# Indictor.net
KiCad netlist of a schematic drawn in Altium Designer
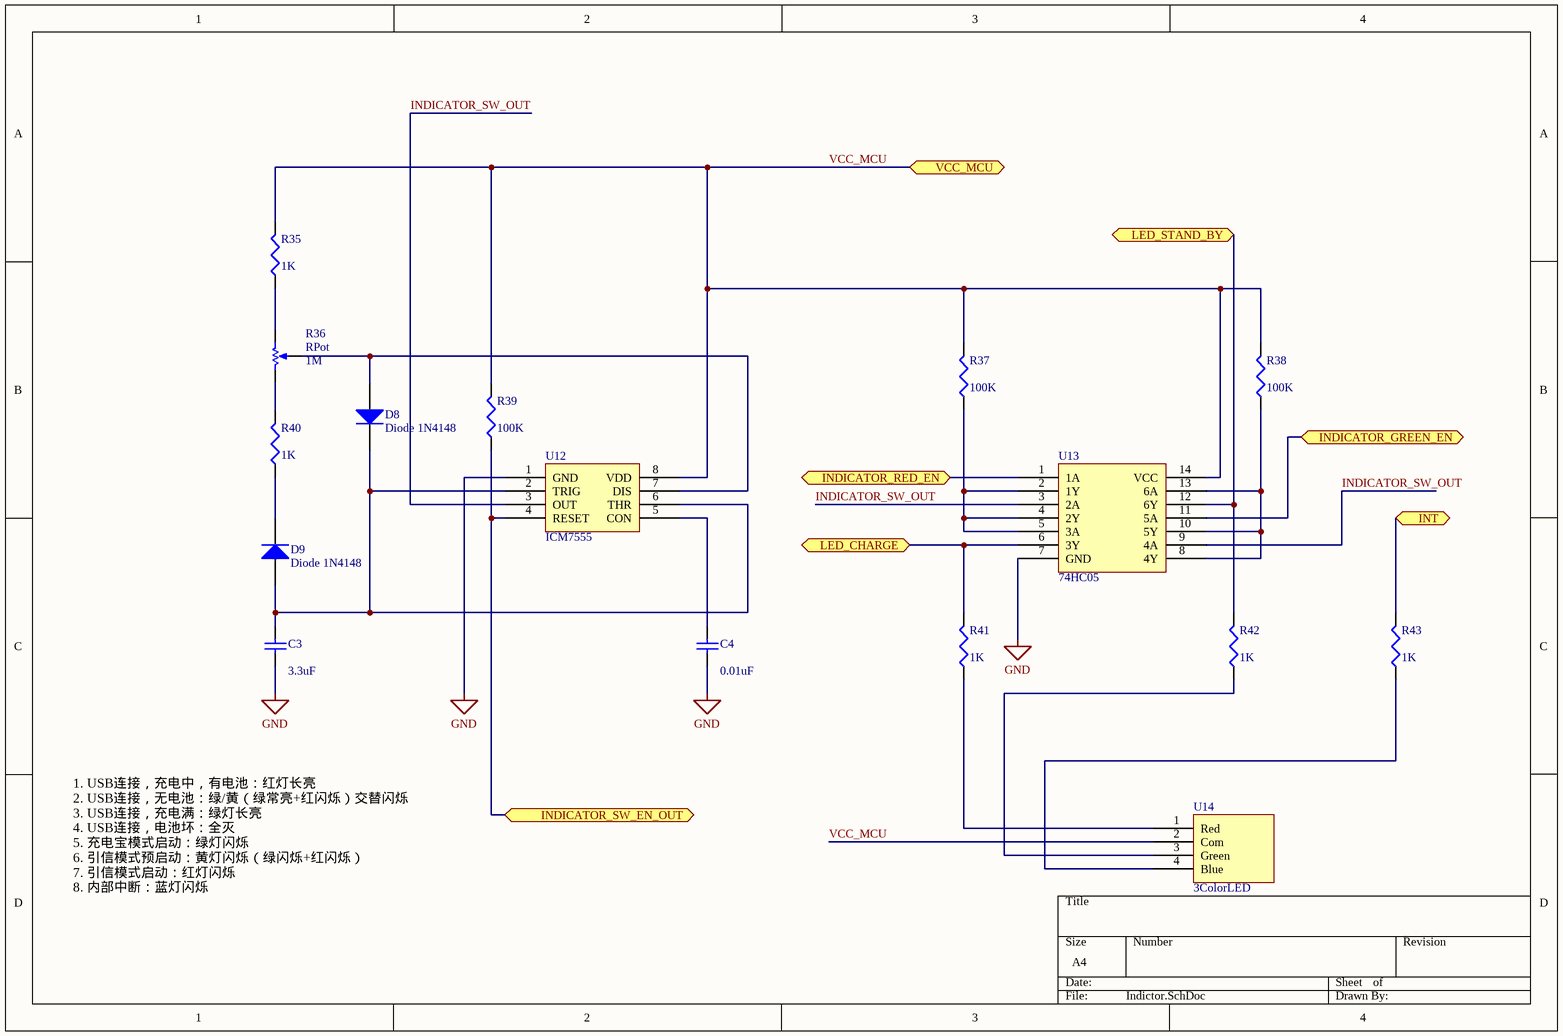
[diagram p0: Indictor.SchDoc]

(export (version "E")
  (design (tool "Eeschema 10.0.6"))
  (components
    (comp (ref "C3")
      (value "3.3uF")
      (footprint "clock:0603")
      (description "Capacitor (Semiconductor SIM Model)")
      (fields (field (name "Comment") "Cap Semi") (field (name "PUBLISHER") "Altium Limited"))
      (libsource (lib "Miscellaneous Devices") (part "Cap Semi"))
    )
    (comp (ref "C4")
      (value "0.01uF")
      (footprint "clock:0603")
      (description "Capacitor (Semiconductor SIM Model)")
      (fields (field (name "Comment") "Cap Semi") (field (name "PUBLISHER") "Altium Limited"))
      (libsource (lib "Miscellaneous Devices") (part "Cap Semi"))
    )
    (comp (ref "D8")
      (value "Diode 1N4148")
      (footprint "clock:1206D")
      (description "1 Amp General Purpose Rectifier")
      (fields (field (name "PUBLISHER") "Altium Limited"))
      (libsource (lib "Miscellaneous Devices") (part "Diode 1N4005"))
    )
    (comp (ref "D9")
      (value "Diode 1N4148")
      (footprint "clock:1206D")
      (description "1 Amp General Purpose Rectifier")
      (fields (field (name "PUBLISHER") "Altium Limited"))
      (libsource (lib "Miscellaneous Devices") (part "Diode 1N4005"))
    )
    (comp (ref "R35")
      (value "1K")
      (footprint "clock:0603")
      (description "Resistor")
      (fields (field (name "Comment") "Res3") (field (name "PUBLISHER") "Altium Limited"))
      (libsource (lib "Miscellaneous Devices") (part "Res3"))
    )
    (comp (ref "R36")
      (value "RPot")
      (footprint "clock:VR5")
      (description "Potentiometer")
      (fields (field (name "ALTIUM_VALUE") "1M") (field (name "PUBLISHER") "Altium Limited"))
      (libsource (lib "Miscellaneous Devices") (part "RPot"))
    )
    (comp (ref "R37")
      (value "100K")
      (footprint "clock:0603")
      (description "Resistor")
      (fields (field (name "Comment") "Res3") (field (name "PUBLISHER") "Altium Limited"))
      (libsource (lib "Miscellaneous Devices") (part "Res3"))
    )
    (comp (ref "R38")
      (value "100K")
      (footprint "clock:0603")
      (description "Resistor")
      (fields (field (name "Comment") "Res3") (field (name "PUBLISHER") "Altium Limited"))
      (libsource (lib "Miscellaneous Devices") (part "Res3"))
    )
    (comp (ref "R39")
      (value "100K")
      (footprint "clock:0603")
      (description "Resistor")
      (fields (field (name "Comment") "Res3") (field (name "PUBLISHER") "Altium Limited"))
      (libsource (lib "Miscellaneous Devices") (part "Res3"))
    )
    (comp (ref "R40")
      (value "1K")
      (footprint "clock:0603")
      (description "Resistor")
      (fields (field (name "Comment") "Res3") (field (name "PUBLISHER") "Altium Limited"))
      (libsource (lib "Miscellaneous Devices") (part "Res3"))
    )
    (comp (ref "R41")
      (value "1K")
      (footprint "clock:0603")
      (description "Resistor")
      (fields (field (name "Comment") "Res3") (field (name "PUBLISHER") "Altium Limited"))
      (libsource (lib "Miscellaneous Devices") (part "Res3"))
    )
    (comp (ref "R42")
      (value "1K")
      (footprint "clock:0603")
      (description "Resistor")
      (fields (field (name "Comment") "Res3") (field (name "PUBLISHER") "Altium Limited"))
      (libsource (lib "Miscellaneous Devices") (part "Res3"))
    )
    (comp (ref "R43")
      (value "1K")
      (footprint "clock:0603")
      (description "Resistor")
      (fields (field (name "Comment") "Res3") (field (name "PUBLISHER") "Altium Limited"))
      (libsource (lib "Miscellaneous Devices") (part "Res3"))
    )
    (comp (ref "U12") (value "ICM7555") (footprint "clock:SOP8") (libsource (lib "clock") (part "ICM7555")))
    (comp (ref "U13") (value "74HC05") (footprint "TSSOP14") (libsource (lib "clock") (part "74HC05")))
    (comp (ref "U14")
      (value "3ColorLED")
      (footprint "clock:3COLOR-LED")
      (libsource (lib "clock") (part "3ColorLED"))
    )
  )
  (nets
    (net (code "1") (name "/INDICATOR_GREEN_EN") (class "Default")
      (node (ref "U13") (pin "11") (pinfunction "5A_11") (pintype "passive"))
    )
    (net (code "2") (name "/INDICATOR_RED_EN") (class "Default")
      (node (ref "U13") (pin "1") (pinfunction "1A_1") (pintype "passive"))
    )
    (net (code "3") (name "/INDICATOR_SW_EN_OUT") (class "Default")
      (node (ref "R39") (pin "1") (pinfunction "1_1") (pintype "passive"))
      (node (ref "U12") (pin "4") (pinfunction "RESET_4") (pintype "passive"))
    )
    (net (code "4") (name "/INDICATOR_SW_OUT") (class "Default")
      (node (ref "U12") (pin "3") (pinfunction "OUT_3") (pintype "passive"))
      (node (ref "U13") (pin "3") (pinfunction "2A_3") (pintype "passive"))
      (node (ref "U13") (pin "9") (pinfunction "4A_9") (pintype "passive"))
    )
    (net (code "5") (name "/INT") (class "Default")
      (node (ref "R43") (pin "2") (pinfunction "2_2") (pintype "passive"))
    )
    (net (code "6") (name "/LED_CHARGE") (class "Default")
      (node (ref "R41") (pin "2") (pinfunction "2_2") (pintype "passive"))
      (node (ref "U13") (pin "6") (pinfunction "3Y_6") (pintype "passive"))
    )
    (net (code "7") (name "/LED_STAND_BY") (class "Default")
      (node (ref "R42") (pin "2") (pinfunction "2_2") (pintype "passive"))
      (node (ref "U13") (pin "12") (pinfunction "6Y_12") (pintype "passive"))
    )
    (net (code "8") (name "/VCC_MCU") (class "Default")
      (node (ref "R35") (pin "2") (pinfunction "2_2") (pintype "passive"))
      (node (ref "R37") (pin "2") (pinfunction "2_2") (pintype "passive"))
      (node (ref "R38") (pin "2") (pinfunction "2_2") (pintype "passive"))
      (node (ref "R39") (pin "2") (pinfunction "2_2") (pintype "passive"))
      (node (ref "U12") (pin "8") (pinfunction "VDD_8") (pintype "passive"))
      (node (ref "U13") (pin "14") (pinfunction "VCC_14") (pintype "passive"))
      (node (ref "U14") (pin "2") (pinfunction "Com_2") (pintype "passive"))
    )
    (net (code "9") (name "GND") (class "Default")
      (node (ref "C3") (pin "1") (pinfunction "1_1") (pintype "passive"))
      (node (ref "C4") (pin "1") (pinfunction "1_1") (pintype "passive"))
      (node (ref "U12") (pin "1") (pinfunction "GND_1") (pintype "passive"))
      (node (ref "U13") (pin "7") (pinfunction "GND_7") (pintype "passive"))
    )
    (net (code "10") (name "Net-(D8-A)") (class "Default")
      (node (ref "D8") (pin "1") (pinfunction "A_1") (pintype "passive"))
      (node (ref "R36") (pin "3") (pinfunction "TAP_3") (pintype "passive"))
      (node (ref "U12") (pin "7") (pinfunction "DIS_7") (pintype "passive"))
    )
    (net (code "11") (name "Net-(D8-K)") (class "Default")
      (node (ref "C3") (pin "2") (pinfunction "2_2") (pintype "passive"))
      (node (ref "D8") (pin "2") (pinfunction "K_2") (pintype "passive"))
      (node (ref "D9") (pin "1") (pinfunction "A_1") (pintype "passive"))
      (node (ref "U12") (pin "2") (pinfunction "TRIG_2") (pintype "passive"))
      (node (ref "U12") (pin "6") (pinfunction "THR_6") (pintype "passive"))
    )
    (net (code "12") (name "Net-(D9-K)") (class "Default")
      (node (ref "D9") (pin "2") (pinfunction "K_2") (pintype "passive"))
      (node (ref "R40") (pin "1") (pinfunction "1_1") (pintype "passive"))
    )
    (net (code "13") (name "Net-(R36-BOT)") (class "Default")
      (node (ref "R36") (pin "2") (pinfunction "BOT_2") (pintype "passive"))
      (node (ref "R40") (pin "2") (pinfunction "2_2") (pintype "passive"))
    )
    (net (code "14") (name "Net-(R36-TOP)") (class "Default")
      (node (ref "R35") (pin "1") (pinfunction "1_1") (pintype "passive"))
      (node (ref "R36") (pin "1") (pinfunction "TOP_1") (pintype "passive"))
    )
    (net (code "15") (name "Net-(U12-CON)") (class "Default")
      (node (ref "C4") (pin "2") (pinfunction "2_2") (pintype "passive"))
      (node (ref "U12") (pin "5") (pinfunction "CON_5") (pintype "passive"))
    )
    (net (code "16") (name "Net-(U13-1Y)") (class "Default")
      (node (ref "R37") (pin "1") (pinfunction "1_1") (pintype "passive"))
      (node (ref "U13") (pin "2") (pinfunction "1Y_2") (pintype "passive"))
      (node (ref "U13") (pin "4") (pinfunction "2Y_4") (pintype "passive"))
      (node (ref "U13") (pin "5") (pinfunction "3A_5") (pintype "passive"))
    )
    (net (code "17") (name "Net-(U13-4Y)") (class "Default")
      (node (ref "R38") (pin "1") (pinfunction "1_1") (pintype "passive"))
      (node (ref "U13") (pin "10") (pinfunction "5Y_10") (pintype "passive"))
      (node (ref "U13") (pin "13") (pinfunction "6A_13") (pintype "passive"))
      (node (ref "U13") (pin "8") (pinfunction "4Y_8") (pintype "passive"))
    )
    (net (code "18") (name "Net-(U14-Blue)") (class "Default")
      (node (ref "R43") (pin "1") (pinfunction "1_1") (pintype "passive"))
      (node (ref "U14") (pin "4") (pinfunction "Blue_4") (pintype "passive"))
    )
    (net (code "19") (name "Net-(U14-Green)") (class "Default")
      (node (ref "R42") (pin "1") (pinfunction "1_1") (pintype "passive"))
      (node (ref "U14") (pin "3") (pinfunction "Green_3") (pintype "passive"))
    )
    (net (code "20") (name "Net-(U14-Red)") (class "Default")
      (node (ref "R41") (pin "1") (pinfunction "1_1") (pintype "passive"))
      (node (ref "U14") (pin "1") (pinfunction "Red_1") (pintype "passive"))
    )
  )
)
